# CONN.net
KiCad netlist of a schematic drawn in Altium Designer
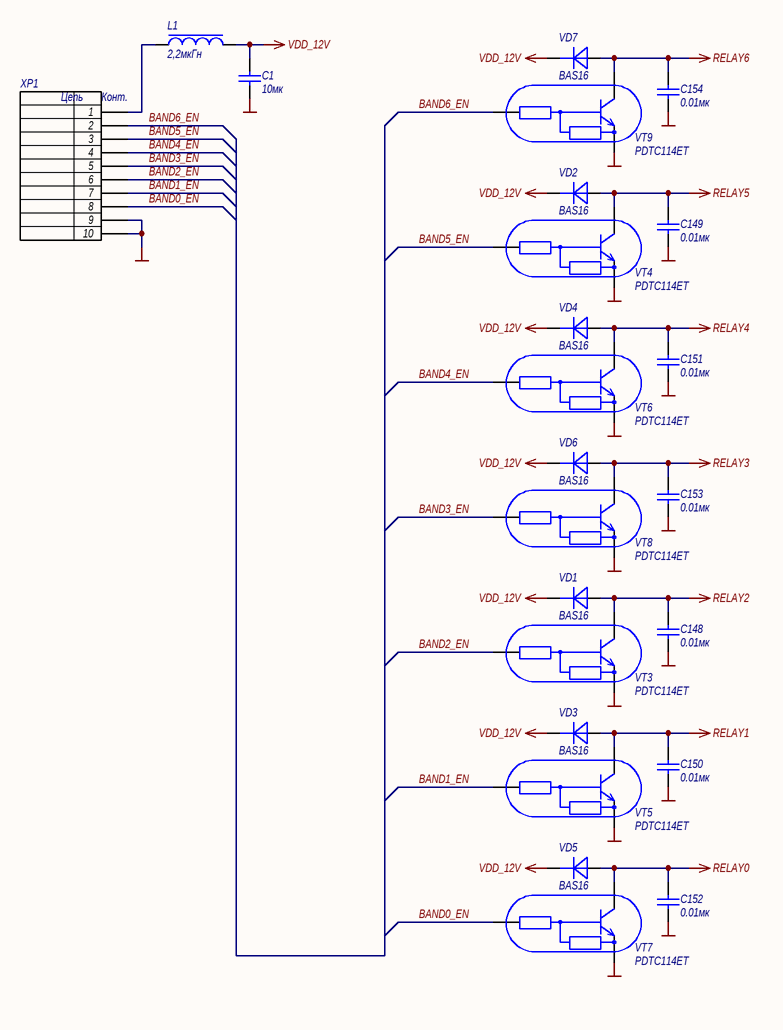
[diagram p0: CONN.SchDoc]

(export (version "E")
  (design (tool "Eeschema 10.0.6"))
  (components
    (comp (ref "C1")
      (value "10мк")
      (footprint "CAPC3225X27L")
      (description "Кер. ЧИП-конденсатор")
      (fields (field (name "MANUFACTURER") "Murata") (field (name "TOLERANCE") "±20%"))
      (libsource (lib "nels_caps") (part "Кер.ЧИП конд. 1210 10мкФ X5R 20% 50В"))
    )
    (comp (ref "C148")
      (value "0.01мк")
      (footprint "CAPC1005X06N")
      (description "Кер. ЧИП-конденсатор")
      (fields (field (name "TOLERANCE") "±20%"))
      (libsource (lib "nels_caps") (part "Кер.ЧИП конд. 0402 0.01мкФ X7R 10%, 50В"))
    )
    (comp (ref "C149")
      (value "0.01мк")
      (footprint "CAPC1005X06N")
      (description "Кер. ЧИП-конденсатор")
      (fields (field (name "TOLERANCE") "±20%"))
      (libsource (lib "nels_caps") (part "Кер.ЧИП конд. 0402 0.01мкФ X7R 10%, 50В"))
    )
    (comp (ref "C150")
      (value "0.01мк")
      (footprint "CAPC1005X06N")
      (description "Кер. ЧИП-конденсатор")
      (fields (field (name "TOLERANCE") "±20%"))
      (libsource (lib "nels_caps") (part "Кер.ЧИП конд. 0402 0.01мкФ X7R 10%, 50В"))
    )
    (comp (ref "C151")
      (value "0.01мк")
      (footprint "CAPC1005X06N")
      (description "Кер. ЧИП-конденсатор")
      (fields (field (name "TOLERANCE") "±20%"))
      (libsource (lib "nels_caps") (part "Кер.ЧИП конд. 0402 0.01мкФ X7R 10%, 50В"))
    )
    (comp (ref "C152")
      (value "0.01мк")
      (footprint "CAPC1005X06N")
      (description "Кер. ЧИП-конденсатор")
      (fields (field (name "TOLERANCE") "±20%"))
      (libsource (lib "nels_caps") (part "Кер.ЧИП конд. 0402 0.01мкФ X7R 10%, 50В"))
    )
    (comp (ref "C153")
      (value "0.01мк")
      (footprint "CAPC1005X06N")
      (description "Кер. ЧИП-конденсатор")
      (fields (field (name "TOLERANCE") "±20%"))
      (libsource (lib "nels_caps") (part "Кер.ЧИП конд. 0402 0.01мкФ X7R 10%, 50В"))
    )
    (comp (ref "C154")
      (value "0.01мк")
      (footprint "CAPC1005X06N")
      (description "Кер. ЧИП-конденсатор")
      (fields (field (name "TOLERANCE") "±20%"))
      (libsource (lib "nels_caps") (part "Кер.ЧИП конд. 0402 0.01мкФ X7R 10%, 50В"))
    )
    (comp (ref "L1")
      (value "2,2мкГн")
      (footprint "CSAB0420")
      (description "Molding Power Choke")
      (fields
        (field (name "MANUFACTURER") "Vishay")
        (field (name "MANUFACTURERPARTNUMBER") "IHLP1616ABER1R0M11")
      )
      (libsource (lib "nels_ind") (part "ЧИП индуктивность CSAB0420-2R2M"))
    )
    (comp (ref "VD1")
      (value "BAS16")
      (footprint "SOT23_N")
      (description "High-speed switching diodes")
      (fields (field (name "MANUFACTURER") "Nexperia"))
      (libsource (lib "nels_other") (part "ЧИП диод BAS16"))
    )
    (comp (ref "VD2")
      (value "BAS16")
      (footprint "SOT23_N")
      (description "High-speed switching diodes")
      (fields (field (name "MANUFACTURER") "Nexperia"))
      (libsource (lib "nels_other") (part "ЧИП диод BAS16"))
    )
    (comp (ref "VD3")
      (value "BAS16")
      (footprint "SOT23_N")
      (description "High-speed switching diodes")
      (fields (field (name "MANUFACTURER") "Nexperia"))
      (libsource (lib "nels_other") (part "ЧИП диод BAS16"))
    )
    (comp (ref "VD4")
      (value "BAS16")
      (footprint "SOT23_N")
      (description "High-speed switching diodes")
      (fields (field (name "MANUFACTURER") "Nexperia"))
      (libsource (lib "nels_other") (part "ЧИП диод BAS16"))
    )
    (comp (ref "VD5")
      (value "BAS16")
      (footprint "SOT23_N")
      (description "High-speed switching diodes")
      (fields (field (name "MANUFACTURER") "Nexperia"))
      (libsource (lib "nels_other") (part "ЧИП диод BAS16"))
    )
    (comp (ref "VD6")
      (value "BAS16")
      (footprint "SOT23_N")
      (description "High-speed switching diodes")
      (fields (field (name "MANUFACTURER") "Nexperia"))
      (libsource (lib "nels_other") (part "ЧИП диод BAS16"))
    )
    (comp (ref "VD7")
      (value "BAS16")
      (footprint "SOT23_N")
      (description "High-speed switching diodes")
      (fields (field (name "MANUFACTURER") "Nexperia"))
      (libsource (lib "nels_other") (part "ЧИП диод BAS16"))
    )
    (comp (ref "VT3")
      (value "PDTC114ET")
      (footprint "SOT23_N")
      (description "NPN resistor-equipped transistors;  R1 = 10 k, R2 = 10")
      (libsource (lib "nels_other") (part "ЧИП транзистор PDTC114ET"))
    )
    (comp (ref "VT4")
      (value "PDTC114ET")
      (footprint "SOT23_N")
      (description "NPN resistor-equipped transistors;  R1 = 10 k, R2 = 10")
      (libsource (lib "nels_other") (part "ЧИП транзистор PDTC114ET"))
    )
    (comp (ref "VT5")
      (value "PDTC114ET")
      (footprint "SOT23_N")
      (description "NPN resistor-equipped transistors;  R1 = 10 k, R2 = 10")
      (libsource (lib "nels_other") (part "ЧИП транзистор PDTC114ET"))
    )
    (comp (ref "VT6")
      (value "PDTC114ET")
      (footprint "SOT23_N")
      (description "NPN resistor-equipped transistors;  R1 = 10 k, R2 = 10")
      (libsource (lib "nels_other") (part "ЧИП транзистор PDTC114ET"))
    )
    (comp (ref "VT7")
      (value "PDTC114ET")
      (footprint "SOT23_N")
      (description "NPN resistor-equipped transistors;  R1 = 10 k, R2 = 10")
      (libsource (lib "nels_other") (part "ЧИП транзистор PDTC114ET"))
    )
    (comp (ref "VT8")
      (value "PDTC114ET")
      (footprint "SOT23_N")
      (description "NPN resistor-equipped transistors;  R1 = 10 k, R2 = 10")
      (libsource (lib "nels_other") (part "ЧИП транзистор PDTC114ET"))
    )
    (comp (ref "VT9")
      (value "PDTC114ET")
      (footprint "SOT23_N")
      (description "NPN resistor-equipped transistors;  R1 = 10 k, R2 = 10")
      (libsource (lib "nels_other") (part "ЧИП транзистор PDTC114ET"))
    )
    (comp (ref "XP1")
      (value "FH12-10S-0.5SVA")
      (footprint "FH12-10S-0.5SH")
      (description "0.5mm  Pitch FPC/FFC Connector FH12 Series")
      (fields (field (name "MANUFACTURER") "Hirose"))
      (libsource (lib "nels_conn") (part "Соединитель FH12-10S-0.5SVA"))
    )
  )
  (nets
    (net (code "1") (name "/BAND0_EN") (class "Default")
      (node (ref "VT7") (pin "1") (pinfunction "B_1") (pintype "passive"))
      (node (ref "XP1") (pin "8") (pinfunction "8_8") (pintype "passive"))
    )
    (net (code "2") (name "/BAND1_EN") (class "Default")
      (node (ref "VT5") (pin "1") (pinfunction "B_1") (pintype "passive"))
      (node (ref "XP1") (pin "7") (pinfunction "7_7") (pintype "passive"))
    )
    (net (code "3") (name "/BAND2_EN") (class "Default")
      (node (ref "VT3") (pin "1") (pinfunction "B_1") (pintype "passive"))
      (node (ref "XP1") (pin "6") (pinfunction "6_6") (pintype "passive"))
    )
    (net (code "4") (name "/BAND3_EN") (class "Default")
      (node (ref "VT8") (pin "1") (pinfunction "B_1") (pintype "passive"))
      (node (ref "XP1") (pin "5") (pinfunction "5_5") (pintype "passive"))
    )
    (net (code "5") (name "/BAND4_EN") (class "Default")
      (node (ref "VT6") (pin "1") (pinfunction "B_1") (pintype "passive"))
      (node (ref "XP1") (pin "4") (pinfunction "4_4") (pintype "passive"))
    )
    (net (code "6") (name "/BAND5_EN") (class "Default")
      (node (ref "VT4") (pin "1") (pinfunction "B_1") (pintype "passive"))
      (node (ref "XP1") (pin "3") (pinfunction "3_3") (pintype "passive"))
    )
    (net (code "7") (name "/BAND6_EN") (class "Default")
      (node (ref "VT9") (pin "1") (pinfunction "B_1") (pintype "passive"))
      (node (ref "XP1") (pin "2") (pinfunction "2_2") (pintype "passive"))
    )
    (net (code "8") (name "GND") (class "Default")
      (node (ref "C1") (pin "1") (pinfunction "1_1") (pintype "passive"))
      (node (ref "C148") (pin "1") (pinfunction "1_1") (pintype "passive"))
      (node (ref "C149") (pin "1") (pinfunction "1_1") (pintype "passive"))
      (node (ref "C150") (pin "1") (pinfunction "1_1") (pintype "passive"))
      (node (ref "C151") (pin "1") (pinfunction "1_1") (pintype "passive"))
      (node (ref "C152") (pin "1") (pinfunction "1_1") (pintype "passive"))
      (node (ref "C153") (pin "1") (pinfunction "1_1") (pintype "passive"))
      (node (ref "C154") (pin "1") (pinfunction "1_1") (pintype "passive"))
      (node (ref "VT3") (pin "2") (pinfunction "E_2") (pintype "passive"))
      (node (ref "VT4") (pin "2") (pinfunction "E_2") (pintype "passive"))
      (node (ref "VT5") (pin "2") (pinfunction "E_2") (pintype "passive"))
      (node (ref "VT6") (pin "2") (pinfunction "E_2") (pintype "passive"))
      (node (ref "VT7") (pin "2") (pinfunction "E_2") (pintype "passive"))
      (node (ref "VT8") (pin "2") (pinfunction "E_2") (pintype "passive"))
      (node (ref "VT9") (pin "2") (pinfunction "E_2") (pintype "passive"))
      (node (ref "XP1") (pin "10") (pinfunction "10_10") (pintype "passive"))
      (node (ref "XP1") (pin "9") (pinfunction "9_9") (pintype "passive"))
    )
    (net (code "9") (name "Net-(L1-Pad1)") (class "Default")
      (node (ref "L1") (pin "1") (pinfunction "1_1") (pintype "passive"))
      (node (ref "XP1") (pin "1") (pinfunction "1_1") (pintype "passive"))
    )
    (net (code "10") (name "RELAY0") (class "Default")
      (node (ref "C152") (pin "2") (pinfunction "2_2") (pintype "passive"))
      (node (ref "VD5") (pin "1") (pinfunction "A_1") (pintype "passive"))
      (node (ref "VT7") (pin "3") (pinfunction "C_3") (pintype "passive"))
    )
    (net (code "11") (name "RELAY1") (class "Default")
      (node (ref "C150") (pin "2") (pinfunction "2_2") (pintype "passive"))
      (node (ref "VD3") (pin "1") (pinfunction "A_1") (pintype "passive"))
      (node (ref "VT5") (pin "3") (pinfunction "C_3") (pintype "passive"))
    )
    (net (code "12") (name "RELAY2") (class "Default")
      (node (ref "C148") (pin "2") (pinfunction "2_2") (pintype "passive"))
      (node (ref "VD1") (pin "1") (pinfunction "A_1") (pintype "passive"))
      (node (ref "VT3") (pin "3") (pinfunction "C_3") (pintype "passive"))
    )
    (net (code "13") (name "RELAY3") (class "Default")
      (node (ref "C153") (pin "2") (pinfunction "2_2") (pintype "passive"))
      (node (ref "VD6") (pin "1") (pinfunction "A_1") (pintype "passive"))
      (node (ref "VT8") (pin "3") (pinfunction "C_3") (pintype "passive"))
    )
    (net (code "14") (name "RELAY4") (class "Default")
      (node (ref "C151") (pin "2") (pinfunction "2_2") (pintype "passive"))
      (node (ref "VD4") (pin "1") (pinfunction "A_1") (pintype "passive"))
      (node (ref "VT6") (pin "3") (pinfunction "C_3") (pintype "passive"))
    )
    (net (code "15") (name "RELAY5") (class "Default")
      (node (ref "C149") (pin "2") (pinfunction "2_2") (pintype "passive"))
      (node (ref "VD2") (pin "1") (pinfunction "A_1") (pintype "passive"))
      (node (ref "VT4") (pin "3") (pinfunction "C_3") (pintype "passive"))
    )
    (net (code "16") (name "RELAY6") (class "Default")
      (node (ref "C154") (pin "2") (pinfunction "2_2") (pintype "passive"))
      (node (ref "VD7") (pin "1") (pinfunction "A_1") (pintype "passive"))
      (node (ref "VT9") (pin "3") (pinfunction "C_3") (pintype "passive"))
    )
    (net (code "17") (name "VDD_12V") (class "Default")
      (node (ref "C1") (pin "2") (pinfunction "2_2") (pintype "passive"))
      (node (ref "L1") (pin "2") (pinfunction "2_2") (pintype "passive"))
      (node (ref "VD1") (pin "3") (pinfunction "K_3") (pintype "passive"))
      (node (ref "VD2") (pin "3") (pinfunction "K_3") (pintype "passive"))
      (node (ref "VD3") (pin "3") (pinfunction "K_3") (pintype "passive"))
      (node (ref "VD4") (pin "3") (pinfunction "K_3") (pintype "passive"))
      (node (ref "VD5") (pin "3") (pinfunction "K_3") (pintype "passive"))
      (node (ref "VD6") (pin "3") (pinfunction "K_3") (pintype "passive"))
      (node (ref "VD7") (pin "3") (pinfunction "K_3") (pintype "passive"))
    )
  )
)
